# myf17.net
KiCad netlist of a schematic drawn in EAGLE
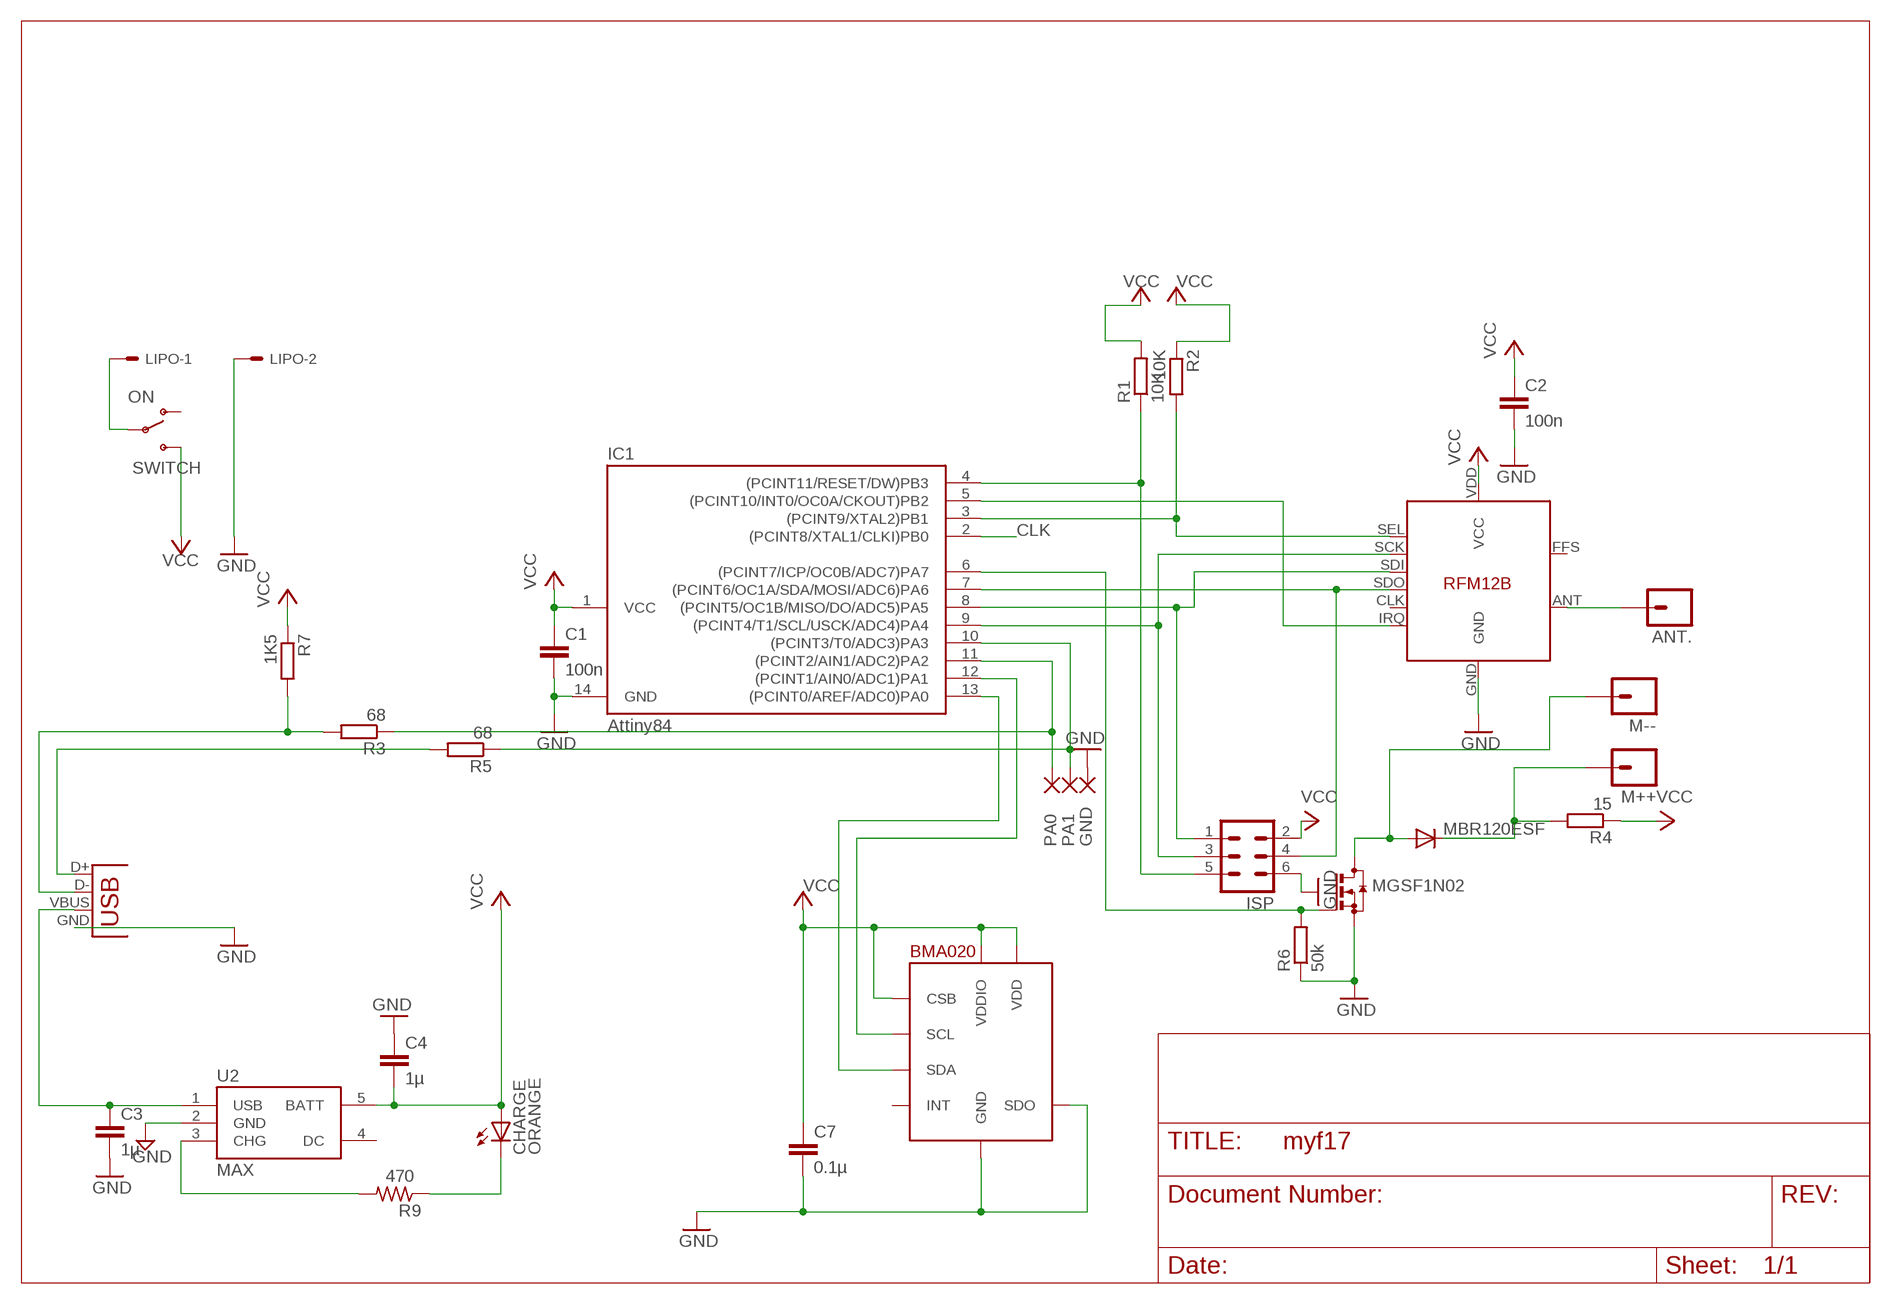
[diagram p0: schematic, sheet 1]

(export (version "E")
  (design (tool "Eeschema 10.0.6"))
  (components
    (comp (ref "ANT.")
      (value "M01PTH")
      (footprint "eagle-import:1X01")
      (libsource (lib "eagle-import") (part "M01PTH"))
    )
    (comp (ref "BMA020")
      (value "BMA020")
      (footprint "eagle-import:LBA-12")
      (libsource (lib "eagle-import") (part "BMA020"))
    )
    (comp (ref "C1")
      (value "100n")
      (footprint "eagle-import:C0603K")
      (libsource (lib "eagle-import") (part "C-EUC0603K"))
    )
    (comp (ref "C2")
      (value "100n")
      (footprint "eagle-import:C0603K")
      (libsource (lib "eagle-import") (part "C-EUC0603K"))
    )
    (comp (ref "C3")
      (value "1µ")
      (footprint "eagle-import:0603-CAP")
      (libsource (lib "eagle-import") (part "CAP0603-CAP"))
    )
    (comp (ref "C4")
      (value "1µ")
      (footprint "eagle-import:0603-CAP")
      (libsource (lib "eagle-import") (part "CAP0603-CAP"))
    )
    (comp (ref "C7")
      (value "0.1µ")
      (footprint "eagle-import:0603-CAP")
      (libsource (lib "eagle-import") (part "CAP0603-CAP"))
    )
    (comp (ref "CHARGE")
      (value "ORANGE")
      (footprint "eagle-import:LED-0603")
      (libsource (lib "eagle-import") (part "LED0603"))
    )
    (comp (ref "GND")
      (value "SMD2")
      (footprint "eagle-import:SMD1,27-2,54")
      (libsource (lib "eagle-import") (part "SMD2"))
    )
    (comp (ref "IC1")
      (value "Attiny84")
      (footprint "eagle-import:SOIC14")
      (libsource (lib "eagle-import") (part "TINY24/44/84-SSU"))
    )
    (comp (ref "ISP")
      (value "MA03-2S")
      (footprint "eagle-import:MA03-2-0.8")
      (libsource (lib "eagle-import") (part "MA03-2S"))
    )
    (comp (ref "LIPO")
      (value "SM02B-SRSS-TB")
      (footprint "eagle-import:SM02B-SRSS-TB")
      (libsource (lib "eagle-import") (part "?M02B-SRSS-TBS"))
    )
    (comp (ref "M++")
      (value "M01PTH")
      (footprint "eagle-import:1X01")
      (libsource (lib "eagle-import") (part "M01PTH"))
    )
    (comp (ref "M--")
      (value "M01PTH")
      (footprint "eagle-import:1X01")
      (libsource (lib "eagle-import") (part "M01PTH"))
    )
    (comp (ref "MBR120ESF")
      (value "CGRM4001-G")
      (footprint "eagle-import:SOD-123_MINI-SMA")
      (libsource (lib "eagle-import") (part "CGRM400-G1"))
    )
    (comp (ref "MGSF1N02")
      (value "BSS123")
      (footprint "eagle-import:SOT23")
      (libsource (lib "eagle-import") (part "BSS123"))
    )
    (comp (ref "PA0")
      (value "SMD2")
      (footprint "eagle-import:SMD1,27-2,54")
      (libsource (lib "eagle-import") (part "SMD2"))
    )
    (comp (ref "PA1")
      (value "SMD2")
      (footprint "eagle-import:SMD1,27-2,54")
      (libsource (lib "eagle-import") (part "SMD2"))
    )
    (comp (ref "R1")
      (value "10K")
      (footprint "eagle-import:R0603")
      (libsource (lib "eagle-import") (part "R-EU_R0603"))
    )
    (comp (ref "R2")
      (value "10K")
      (footprint "eagle-import:R0603")
      (libsource (lib "eagle-import") (part "R-EU_R0603"))
    )
    (comp (ref "R3")
      (value "68")
      (footprint "eagle-import:R0603")
      (libsource (lib "eagle-import") (part "R-EU_R0603"))
    )
    (comp (ref "R4")
      (value "15")
      (footprint "eagle-import:R0603")
      (libsource (lib "eagle-import") (part "R-EU_R0603"))
    )
    (comp (ref "R5")
      (value "68")
      (footprint "eagle-import:R0603")
      (libsource (lib "eagle-import") (part "R-EU_R0603"))
    )
    (comp (ref "R6")
      (value "50k")
      (footprint "eagle-import:R0603")
      (libsource (lib "eagle-import") (part "R-EU_R0603"))
    )
    (comp (ref "R7")
      (value "1K5")
      (footprint "eagle-import:R0603")
      (libsource (lib "eagle-import") (part "R-EU_R0603"))
    )
    (comp (ref "R9")
      (value "470")
      (footprint "eagle-import:R0603")
      (libsource (lib "eagle-import") (part "R-US_R0603"))
    )
    (comp (ref "RFM12B")
      (value "RFM12B")
      (footprint "eagle-import:RFM12B")
      (libsource (lib "eagle-import") (part "RFM12B"))
    )
    (comp (ref "SWITCH")
      (value "ON")
      (footprint "eagle-import:SWITCH-SPDT-SMD")
      (libsource (lib "eagle-import") (part "SWITCH-SPDTSMD2"))
    )
    (comp (ref "U2")
      (value "MAX")
      (footprint "eagle-import:SOT23-5")
      (libsource (lib "eagle-import") (part "MAX1555"))
    )
    (comp (ref "USB")
      (value "USB-MICROB")
      (footprint "eagle-import:USB-MICROB")
      (libsource (lib "eagle-import") (part "USB-MICROB"))
    )
  )
  (nets
    (net (code "1") (name "/CLK") (class "Default")
      (node (ref "IC1") (pin "2") (pinfunction "(PCINT8/XTAL1/CLKI)PB0_2") (pintype "bidirectional"))
    )
    (net (code "2") (name "GND") (class "Default")
      (node (ref "BMA020") (pin "P$3") (pinfunction "GND_P$3") (pintype "power_in"))
      (node (ref "BMA020") (pin "P$7") (pinfunction "SDO_P$7") (pintype "bidirectional"))
      (node (ref "C1") (pin "2") (pinfunction "2_2") (pintype "passive"))
      (node (ref "C2") (pin "2") (pinfunction "2_2") (pintype "passive"))
      (node (ref "C3") (pin "2") (pinfunction "2_2") (pintype "passive"))
      (node (ref "C4") (pin "1") (pinfunction "1_1") (pintype "passive"))
      (node (ref "C7") (pin "2") (pinfunction "2_2") (pintype "passive"))
      (node (ref "GND") (pin "1") (pinfunction "P_1") (pintype "passive"))
      (node (ref "IC1") (pin "14") (pinfunction "GND_14") (pintype "power_in"))
      (node (ref "ISP") (pin "6") (pinfunction "6_6") (pintype "passive"))
      (node (ref "LIPO") (pin "2") (pinfunction "S_2") (pintype "passive"))
      (node (ref "MGSF1N02") (pin "2") (pinfunction "S_2") (pintype "passive"))
      (node (ref "R6") (pin "1") (pinfunction "1_1") (pintype "passive"))
      (node (ref "RFM12B") (pin "GND") (pinfunction "GND_GND") (pintype "power_in"))
      (node (ref "U2") (pin "2") (pinfunction "GND_2") (pintype "bidirectional"))
      (node (ref "USB") (pin "GND") (pinfunction "GND_GND") (pintype "bidirectional"))
    )
    (net (code "3") (name "Net-(ANT.-Pad1)") (class "Default")
      (node (ref "ANT.") (pin "1") (pinfunction "1_1") (pintype "passive"))
      (node (ref "RFM12B") (pin "ANT") (pinfunction "ANT_ANT") (pintype "passive"))
    )
    (net (code "4") (name "Net-(BMA020-SCL)") (class "Default")
      (node (ref "BMA020") (pin "P$6") (pinfunction "SCL_P$6") (pintype "bidirectional"))
      (node (ref "IC1") (pin "12") (pinfunction "(PCINT1/AIN0/ADC1)PA1_12") (pintype "bidirectional"))
    )
    (net (code "5") (name "Net-(BMA020-SDA)") (class "Default")
      (node (ref "BMA020") (pin "P$8") (pinfunction "SDA_P$8") (pintype "bidirectional"))
      (node (ref "IC1") (pin "13") (pinfunction "(PCINT0/AREF/ADC0)PA0_13") (pintype "bidirectional"))
    )
    (net (code "6") (name "Net-(CHARGE-PadC)") (class "Default")
      (node (ref "CHARGE") (pin "C") (pinfunction "C_C") (pintype "passive"))
      (node (ref "R9") (pin "1") (pinfunction "1_1") (pintype "passive"))
    )
    (net (code "7") (name "Net-(IC1-(PCINT2{slash}AIN1{slash}ADC2)PA2)") (class "Default")
      (node (ref "IC1") (pin "11") (pinfunction "(PCINT2/AIN1/ADC2)PA2_11") (pintype "bidirectional"))
      (node (ref "PA0") (pin "1") (pinfunction "P_1") (pintype "passive"))
      (node (ref "R3") (pin "1") (pinfunction "1_1") (pintype "passive"))
    )
    (net (code "8") (name "Net-(IC1-(PCINT3{slash}T0{slash}ADC3)PA3)") (class "Default")
      (node (ref "IC1") (pin "10") (pinfunction "(PCINT3/T0/ADC3)PA3_10") (pintype "bidirectional"))
      (node (ref "PA1") (pin "1") (pinfunction "P_1") (pintype "passive"))
      (node (ref "R5") (pin "1") (pinfunction "1_1") (pintype "passive"))
    )
    (net (code "9") (name "Net-(IC1-(PCINT4{slash}T1{slash}SCL{slash}USCK{slash}ADC4)PA4)") (class "Default")
      (node (ref "IC1") (pin "9") (pinfunction "(PCINT4/T1/SCL/USCK/ADC4)PA4_9") (pintype "bidirectional"))
      (node (ref "ISP") (pin "3") (pinfunction "3_3") (pintype "passive"))
      (node (ref "RFM12B") (pin "SCK") (pinfunction "SCK_SCK") (pintype "input"))
    )
    (net (code "10") (name "Net-(IC1-(PCINT5{slash}OC1B{slash}MISO{slash}DO{slash}ADC5)PA5)") (class "Default")
      (node (ref "IC1") (pin "8") (pinfunction "(PCINT5/OC1B/MISO/DO/ADC5)PA5_8") (pintype "bidirectional"))
      (node (ref "ISP") (pin "1") (pinfunction "1_1") (pintype "passive"))
      (node (ref "RFM12B") (pin "SDI") (pinfunction "SDI_SDI") (pintype "input"))
    )
    (net (code "11") (name "Net-(IC1-(PCINT6{slash}OC1A{slash}SDA{slash}MOSI{slash}ADC6)PA6)") (class "Default")
      (node (ref "IC1") (pin "7") (pinfunction "(PCINT6/OC1A/SDA/MOSI/ADC6)PA6_7") (pintype "bidirectional"))
      (node (ref "ISP") (pin "4") (pinfunction "4_4") (pintype "passive"))
      (node (ref "RFM12B") (pin "SDO") (pinfunction "SDO_SDO") (pintype "output"))
    )
    (net (code "12") (name "Net-(IC1-(PCINT7{slash}ICP{slash}OC0B{slash}ADC7)PA7)") (class "Default")
      (node (ref "IC1") (pin "6") (pinfunction "(PCINT7/ICP/OC0B/ADC7)PA7_6") (pintype "bidirectional"))
      (node (ref "MGSF1N02") (pin "1") (pinfunction "G_1") (pintype "passive"))
      (node (ref "R6") (pin "2") (pinfunction "2_2") (pintype "passive"))
    )
    (net (code "13") (name "Net-(IC1-(PCINT9{slash}XTAL2)PB1)") (class "Default")
      (node (ref "IC1") (pin "3") (pinfunction "(PCINT9/XTAL2)PB1_3") (pintype "bidirectional"))
      (node (ref "R2") (pin "2") (pinfunction "2_2") (pintype "passive"))
      (node (ref "RFM12B") (pin "SEL") (pinfunction "SEL_SEL") (pintype "input"))
    )
    (net (code "14") (name "Net-(IC1-(PCINT10{slash}INT0{slash}OC0A{slash}CKOUT)PB2)") (class "Default")
      (node (ref "IC1") (pin "5") (pinfunction "(PCINT10/INT0/OC0A/CKOUT)PB2_5") (pintype "bidirectional"))
      (node (ref "RFM12B") (pin "IRQ") (pinfunction "IRQ_IRQ") (pintype "open_collector"))
    )
    (net (code "15") (name "Net-(IC1-(PCINT11{slash}RESET{slash}DW)PB3)") (class "Default")
      (node (ref "IC1") (pin "4") (pinfunction "(PCINT11/RESET/DW)PB3_4") (pintype "bidirectional"))
      (node (ref "ISP") (pin "5") (pinfunction "5_5") (pintype "passive"))
      (node (ref "R1") (pin "1") (pinfunction "1_1") (pintype "passive"))
    )
    (net (code "16") (name "Net-(LIPOA-S)") (class "Default")
      (node (ref "LIPO") (pin "1") (pinfunction "S_1") (pintype "passive"))
      (node (ref "SWITCH") (pin "2") (pinfunction "P_2") (pintype "passive"))
    )
    (net (code "17") (name "Net-(M++-Pad1)") (class "Default")
      (node (ref "M++") (pin "1") (pinfunction "1_1") (pintype "passive"))
      (node (ref "MBR120ESF") (pin "C") (pinfunction "C_C") (pintype "passive"))
      (node (ref "R4") (pin "2") (pinfunction "2_2") (pintype "passive"))
    )
    (net (code "18") (name "Net-(MGSF1N02-D)") (class "Default")
      (node (ref "M--") (pin "1") (pinfunction "1_1") (pintype "passive"))
      (node (ref "MBR120ESF") (pin "A") (pinfunction "A_A") (pintype "passive"))
      (node (ref "MGSF1N02") (pin "3") (pinfunction "D_3") (pintype "passive"))
    )
    (net (code "19") (name "Net-(R3-Pad2)") (class "Default")
      (node (ref "R3") (pin "2") (pinfunction "2_2") (pintype "passive"))
      (node (ref "R7") (pin "2") (pinfunction "2_2") (pintype "passive"))
      (node (ref "USB") (pin "D-") (pinfunction "D-_D-") (pintype "bidirectional"))
    )
    (net (code "20") (name "Net-(R5-Pad2)") (class "Default")
      (node (ref "R5") (pin "2") (pinfunction "2_2") (pintype "passive"))
      (node (ref "USB") (pin "D+") (pinfunction "D+_D+") (pintype "bidirectional"))
    )
    (net (code "21") (name "Net-(U2-CHG)") (class "Default")
      (node (ref "R9") (pin "2") (pinfunction "2_2") (pintype "passive"))
      (node (ref "U2") (pin "3") (pinfunction "CHG_3") (pintype "bidirectional"))
    )
    (net (code "22") (name "Net-(U2-USB)") (class "Default")
      (node (ref "C3") (pin "1") (pinfunction "1_1") (pintype "passive"))
      (node (ref "U2") (pin "1") (pinfunction "USB_1") (pintype "bidirectional"))
      (node (ref "USB") (pin "VBUS") (pinfunction "VBUS_VBUS") (pintype "bidirectional"))
    )
    (net (code "23") (name "VCC") (class "Default")
      (node (ref "BMA020") (pin "P$2") (pinfunction "VDD_P$2") (pintype "power_in"))
      (node (ref "BMA020") (pin "P$5") (pinfunction "CSB_P$5") (pintype "bidirectional"))
      (node (ref "BMA020") (pin "P$9") (pinfunction "VDDIO_P$9") (pintype "power_in"))
      (node (ref "C1") (pin "1") (pinfunction "1_1") (pintype "passive"))
      (node (ref "C2") (pin "1") (pinfunction "1_1") (pintype "passive"))
      (node (ref "C4") (pin "2") (pinfunction "2_2") (pintype "passive"))
      (node (ref "C7") (pin "1") (pinfunction "1_1") (pintype "passive"))
      (node (ref "CHARGE") (pin "A") (pinfunction "A_A") (pintype "passive"))
      (node (ref "IC1") (pin "1") (pinfunction "VCC_1") (pintype "power_in"))
      (node (ref "ISP") (pin "2") (pinfunction "2_2") (pintype "passive"))
      (node (ref "R1") (pin "2") (pinfunction "2_2") (pintype "passive"))
      (node (ref "R2") (pin "1") (pinfunction "1_1") (pintype "passive"))
      (node (ref "R4") (pin "1") (pinfunction "1_1") (pintype "passive"))
      (node (ref "R7") (pin "1") (pinfunction "1_1") (pintype "passive"))
      (node (ref "RFM12B") (pin "VDD") (pinfunction "VCC_VDD") (pintype "power_in"))
      (node (ref "SWITCH") (pin "3") (pinfunction "S_3") (pintype "passive"))
      (node (ref "U2") (pin "5") (pinfunction "BATT_5") (pintype "bidirectional"))
    )
    (net (code "24") (name "unconnected-(BMA020-INT-PadP$4)") (class "Default")
      (node (ref "BMA020") (pin "P$4") (pinfunction "INT_P$4") (pintype "open_collector"))
    )
    (net (code "25") (name "unconnected-(RFM12B-PadCLK)") (class "Default")
      (node (ref "RFM12B") (pin "CLK") (pinfunction "CLK_CLK") (pintype "output"))
    )
    (net (code "26") (name "unconnected-(RFM12B-PadFFS)") (class "Default")
      (node (ref "RFM12B") (pin "FFS") (pinfunction "FFS_FFS") (pintype "bidirectional"))
    )
    (net (code "27") (name "unconnected-(SWITCH-O-Pad1)") (class "Default")
      (node (ref "SWITCH") (pin "1") (pinfunction "O_1") (pintype "passive"))
    )
    (net (code "28") (name "unconnected-(U2-DC-Pad4)") (class "Default")
      (node (ref "U2") (pin "4") (pinfunction "DC_4") (pintype "bidirectional"))
    )
  )
)
